# LAYOUT.net
KiCad netlist of a schematic drawn in EAGLE
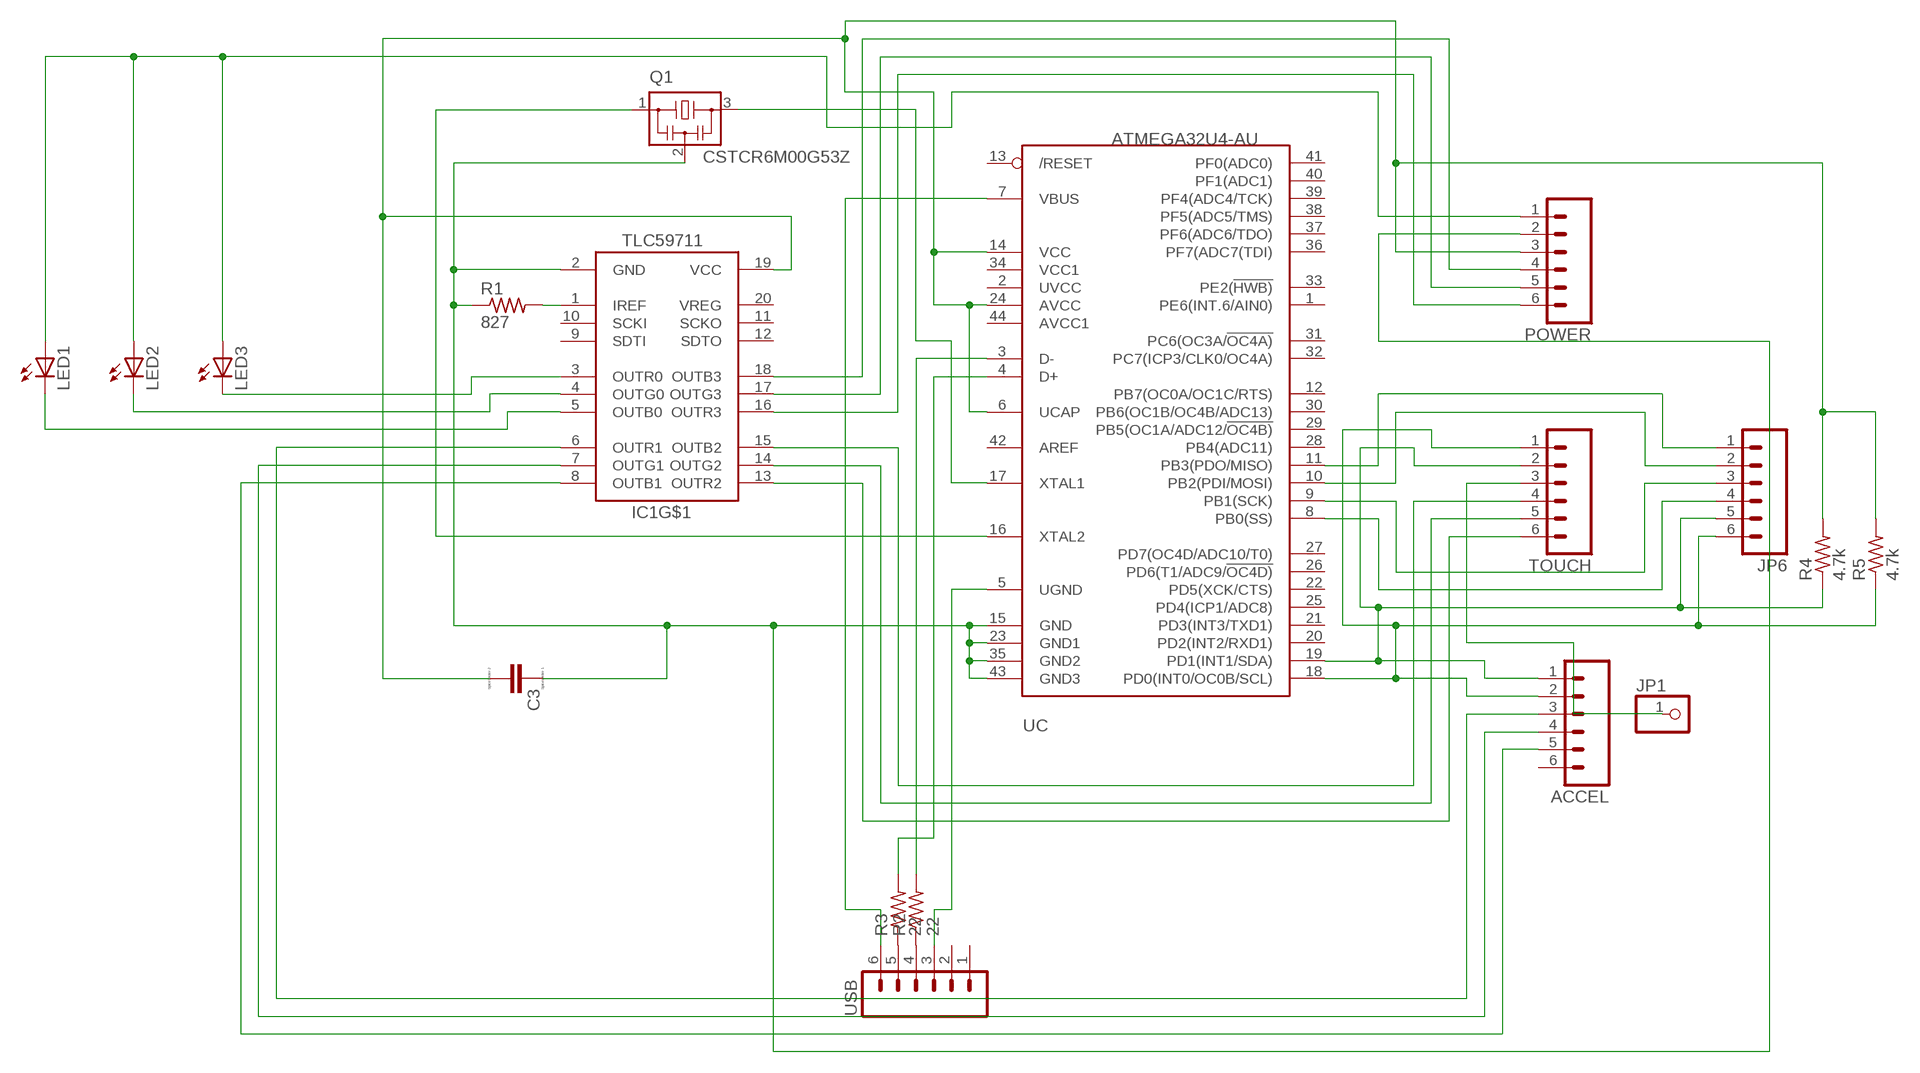
[diagram p0: schematic, sheet 1]

(export (version "E")
  (design (tool "Eeschema 10.0.6"))
  (components
    (comp (ref "ACCEL")
      (value "M06SMD-STRAIGHT")
      (footprint "eagle-import:1X06_SMD_STRAIGHT")
      (libsource (lib "eagle-import") (part "M06SMD-STRAIGHT"))
    )
    (comp (ref "C3")
      (value "CC0603")
      (footprint "eagle-import:C0603")
      (libsource (lib "eagle-import") (part "CC0603"))
    )
    (comp (ref "IC1")
      (value "TLC59711")
      (footprint "eagle-import:HTSSOP20DAP")
      (libsource (lib "eagle-import") (part "TLC59711"))
    )
    (comp (ref "JP1")
      (value "PINHD-1X1")
      (footprint "eagle-import:1X01")
      (libsource (lib "eagle-import") (part "PINHD-1X1"))
    )
    (comp (ref "JP6")
      (value "M06SMD-STRAIGHT")
      (footprint "eagle-import:1X06_SMD_STRAIGHT")
      (libsource (lib "eagle-import") (part "M06SMD-STRAIGHT"))
    )
    (comp (ref "LED1")
      (value "LEDP-LCC-4")
      (footprint "eagle-import:P-LCC-4")
      (libsource (lib "eagle-import") (part "LEDP-LCC-4"))
    )
    (comp (ref "LED2")
      (value "LEDP-LCC-4")
      (footprint "eagle-import:P-LCC-4")
      (libsource (lib "eagle-import") (part "LEDP-LCC-4"))
    )
    (comp (ref "LED3")
      (value "LEDP-LCC-4")
      (footprint "eagle-import:P-LCC-4")
      (libsource (lib "eagle-import") (part "LEDP-LCC-4"))
    )
    (comp (ref "POWER")
      (value "M06SMD-STRAIGHT")
      (footprint "eagle-import:1X06_SMD_STRAIGHT")
      (libsource (lib "eagle-import") (part "M06SMD-STRAIGHT"))
    )
    (comp (ref "Q1")
      (value "CSTCR6M00G53Z")
      (footprint "eagle-import:CSTCR6M")
      (fields (field (name "MPN") "CSTCR6M00G53-R0"))
      (libsource (lib "eagle-import") (part "CSTCR6M00G53Z"))
    )
    (comp (ref "R1")
      (value "827")
      (footprint "eagle-import:R0603")
      (libsource (lib "eagle-import") (part "R-US_R0603"))
    )
    (comp (ref "R2")
      (value "22")
      (footprint "eagle-import:R0603")
      (libsource (lib "eagle-import") (part "R-US_R0603"))
    )
    (comp (ref "R3")
      (value "22")
      (footprint "eagle-import:R0603")
      (libsource (lib "eagle-import") (part "R-US_R0603"))
    )
    (comp (ref "R4")
      (value "4.7k")
      (footprint "eagle-import:R0603")
      (libsource (lib "eagle-import") (part "R-US_R0603"))
    )
    (comp (ref "R5")
      (value "4.7k")
      (footprint "eagle-import:R0603")
      (libsource (lib "eagle-import") (part "R-US_R0603"))
    )
    (comp (ref "TOUCH")
      (value "M06SMD-STRAIGHT")
      (footprint "eagle-import:1X06_SMD_STRAIGHT")
      (libsource (lib "eagle-import") (part "M06SMD-STRAIGHT"))
    )
    (comp (ref "UC")
      (value "ATMEGA32U4-AU")
      (footprint "eagle-import:TQFP44")
      (libsource (lib "eagle-import") (part "ATMEGA32U4-AU"))
    )
    (comp (ref "USB")
      (value "M06SMD-STRAIGHT")
      (footprint "eagle-import:1X06_SMD_STRAIGHT")
      (libsource (lib "eagle-import") (part "M06SMD-STRAIGHT"))
    )
  )
  (nets
    (net (code "1") (name "Net-(IC1A-GND)") (class "Default")
      (node (ref "C3") (pin "1") (pinfunction "1_1") (pintype "passive"))
      (node (ref "IC1") (pin "2") (pinfunction "GND_2") (pintype "power_in"))
      (node (ref "POWER") (pin "2") (pinfunction "2_2") (pintype "passive"))
      (node (ref "Q1") (pin "2") (pinfunction "2_2") (pintype "passive"))
      (node (ref "R1") (pin "1") (pinfunction "1_1") (pintype "passive"))
      (node (ref "UC") (pin "15") (pinfunction "GND_15") (pintype "bidirectional"))
      (node (ref "UC") (pin "23") (pinfunction "GND1_23") (pintype "bidirectional"))
      (node (ref "UC") (pin "35") (pinfunction "GND2_35") (pintype "bidirectional"))
      (node (ref "UC") (pin "43") (pinfunction "GND3_43") (pintype "bidirectional"))
    )
    (net (code "2") (name "Net-(IC1A-IREF)") (class "Default")
      (node (ref "IC1") (pin "1") (pinfunction "IREF_1") (pintype "bidirectional"))
      (node (ref "R1") (pin "2") (pinfunction "2_2") (pintype "passive"))
    )
    (net (code "3") (name "Net-(IC1A-OUTB0)") (class "Default")
      (node (ref "IC1") (pin "5") (pinfunction "OUTB0_5") (pintype "open_collector"))
      (node (ref "LED1") (pin "C@4") (pinfunction "C_C@4") (pintype "passive"))
    )
    (net (code "4") (name "Net-(IC1A-OUTB1)") (class "Default")
      (node (ref "ACCEL") (pin "5") (pinfunction "5_5") (pintype "passive"))
      (node (ref "IC1") (pin "8") (pinfunction "OUTB1_8") (pintype "open_collector"))
    )
    (net (code "5") (name "Net-(IC1A-OUTB2)") (class "Default")
      (node (ref "IC1") (pin "15") (pinfunction "OUTB2_15") (pintype "open_collector"))
      (node (ref "TOUCH") (pin "4") (pinfunction "4_4") (pintype "passive"))
    )
    (net (code "6") (name "Net-(IC1A-OUTB3)") (class "Default")
      (node (ref "IC1") (pin "18") (pinfunction "OUTB3_18") (pintype "open_collector"))
      (node (ref "POWER") (pin "4") (pinfunction "4_4") (pintype "passive"))
    )
    (net (code "7") (name "Net-(IC1A-OUTG0)") (class "Default")
      (node (ref "IC1") (pin "4") (pinfunction "OUTG0_4") (pintype "open_collector"))
      (node (ref "LED2") (pin "C@4") (pinfunction "C_C@4") (pintype "passive"))
    )
    (net (code "8") (name "Net-(IC1A-OUTG1)") (class "Default")
      (node (ref "ACCEL") (pin "4") (pinfunction "4_4") (pintype "passive"))
      (node (ref "IC1") (pin "7") (pinfunction "OUTG1_7") (pintype "open_collector"))
    )
    (net (code "9") (name "Net-(IC1A-OUTG2)") (class "Default")
      (node (ref "IC1") (pin "14") (pinfunction "OUTG2_14") (pintype "open_collector"))
      (node (ref "TOUCH") (pin "5") (pinfunction "5_5") (pintype "passive"))
    )
    (net (code "10") (name "Net-(IC1A-OUTG3)") (class "Default")
      (node (ref "IC1") (pin "17") (pinfunction "OUTG3_17") (pintype "open_collector"))
      (node (ref "POWER") (pin "5") (pinfunction "5_5") (pintype "passive"))
    )
    (net (code "11") (name "Net-(IC1A-OUTR0)") (class "Default")
      (node (ref "IC1") (pin "3") (pinfunction "OUTR0_3") (pintype "open_collector"))
      (node (ref "LED3") (pin "C@4") (pinfunction "C_C@4") (pintype "passive"))
    )
    (net (code "12") (name "Net-(IC1A-OUTR1)") (class "Default")
      (node (ref "ACCEL") (pin "3") (pinfunction "3_3") (pintype "passive"))
      (node (ref "IC1") (pin "6") (pinfunction "OUTR1_6") (pintype "open_collector"))
    )
    (net (code "13") (name "Net-(IC1A-OUTR2)") (class "Default")
      (node (ref "IC1") (pin "13") (pinfunction "OUTR2_13") (pintype "open_collector"))
      (node (ref "TOUCH") (pin "6") (pinfunction "6_6") (pintype "passive"))
    )
    (net (code "14") (name "Net-(IC1A-OUTR3)") (class "Default")
      (node (ref "IC1") (pin "16") (pinfunction "OUTR3_16") (pintype "open_collector"))
      (node (ref "POWER") (pin "6") (pinfunction "6_6") (pintype "passive"))
    )
    (net (code "15") (name "Net-(IC1A-VCC)") (class "Default")
      (node (ref "C3") (pin "2") (pinfunction "2_2") (pintype "passive"))
      (node (ref "IC1") (pin "19") (pinfunction "VCC_19") (pintype "power_in"))
      (node (ref "POWER") (pin "3") (pinfunction "3_3") (pintype "passive"))
      (node (ref "R4") (pin "2") (pinfunction "2_2") (pintype "passive"))
      (node (ref "R5") (pin "2") (pinfunction "2_2") (pintype "passive"))
      (node (ref "UC") (pin "14") (pinfunction "VCC_14") (pintype "bidirectional"))
      (node (ref "UC") (pin "24") (pinfunction "AVCC_24") (pintype "bidirectional"))
      (node (ref "UC") (pin "6") (pinfunction "UCAP_6") (pintype "bidirectional"))
    )
    (net (code "16") (name "Net-(JP1-Pad1)") (class "Default")
      (node (ref "JP1") (pin "1") (pinfunction "1_1") (pintype "passive"))
      (node (ref "TOUCH") (pin "3") (pinfunction "3_3") (pintype "passive"))
    )
    (net (code "17") (name "Net-(LED1-PadA)") (class "Default")
      (node (ref "LED1") (pin "A") (pinfunction "A_A") (pintype "passive"))
      (node (ref "LED2") (pin "A") (pinfunction "A_A") (pintype "passive"))
      (node (ref "LED3") (pin "A") (pinfunction "A_A") (pintype "passive"))
      (node (ref "POWER") (pin "1") (pinfunction "1_1") (pintype "passive"))
    )
    (net (code "18") (name "Net-(R2-Pad1)") (class "Default")
      (node (ref "R2") (pin "1") (pinfunction "1_1") (pintype "passive"))
      (node (ref "USB") (pin "4") (pinfunction "4_4") (pintype "passive"))
    )
    (net (code "19") (name "Net-(R3-Pad1)") (class "Default")
      (node (ref "R3") (pin "1") (pinfunction "1_1") (pintype "passive"))
      (node (ref "USB") (pin "5") (pinfunction "5_5") (pintype "passive"))
    )
    (net (code "20") (name "Net-(UC-D+)") (class "Default")
      (node (ref "R3") (pin "2") (pinfunction "2_2") (pintype "passive"))
      (node (ref "UC") (pin "4") (pinfunction "D+_4") (pintype "bidirectional"))
    )
    (net (code "21") (name "Net-(UC-D-)") (class "Default")
      (node (ref "R2") (pin "2") (pinfunction "2_2") (pintype "passive"))
      (node (ref "UC") (pin "3") (pinfunction "D-_3") (pintype "bidirectional"))
    )
    (net (code "22") (name "Net-(UC-PB0(SS))") (class "Default")
      (node (ref "JP6") (pin "4") (pinfunction "4_4") (pintype "passive"))
      (node (ref "UC") (pin "8") (pinfunction "PB0(SS)_8") (pintype "bidirectional"))
    )
    (net (code "23") (name "Net-(UC-PB1(SCK))") (class "Default")
      (node (ref "JP6") (pin "3") (pinfunction "3_3") (pintype "passive"))
      (node (ref "UC") (pin "9") (pinfunction "PB1(SCK)_9") (pintype "bidirectional"))
    )
    (net (code "24") (name "Net-(UC-PB2(PDI{slash}MOSI))") (class "Default")
      (node (ref "JP6") (pin "2") (pinfunction "2_2") (pintype "passive"))
      (node (ref "UC") (pin "10") (pinfunction "PB2(PDI/MOSI)_10") (pintype "bidirectional"))
    )
    (net (code "25") (name "Net-(UC-PB3(PDO{slash}MISO))") (class "Default")
      (node (ref "JP6") (pin "1") (pinfunction "1_1") (pintype "passive"))
      (node (ref "UC") (pin "11") (pinfunction "PB3(PDO/MISO)_11") (pintype "bidirectional"))
    )
    (net (code "26") (name "Net-(UC-PD0(INT0{slash}OC0B{slash}SCL))") (class "Default")
      (node (ref "ACCEL") (pin "2") (pinfunction "2_2") (pintype "passive"))
      (node (ref "JP6") (pin "6") (pinfunction "6_6") (pintype "passive"))
      (node (ref "R5") (pin "1") (pinfunction "1_1") (pintype "passive"))
      (node (ref "TOUCH") (pin "1") (pinfunction "1_1") (pintype "passive"))
      (node (ref "UC") (pin "18") (pinfunction "PD0(INT0/OC0B/SCL)_18") (pintype "bidirectional"))
    )
    (net (code "27") (name "Net-(UC-PD1(INT1{slash}SDA))") (class "Default")
      (node (ref "ACCEL") (pin "1") (pinfunction "1_1") (pintype "passive"))
      (node (ref "JP6") (pin "5") (pinfunction "5_5") (pintype "passive"))
      (node (ref "R4") (pin "1") (pinfunction "1_1") (pintype "passive"))
      (node (ref "TOUCH") (pin "2") (pinfunction "2_2") (pintype "passive"))
      (node (ref "UC") (pin "19") (pinfunction "PD1(INT1/SDA)_19") (pintype "bidirectional"))
    )
    (net (code "28") (name "Net-(UC-UGND)") (class "Default")
      (node (ref "UC") (pin "5") (pinfunction "UGND_5") (pintype "bidirectional"))
      (node (ref "USB") (pin "3") (pinfunction "3_3") (pintype "passive"))
    )
    (net (code "29") (name "Net-(UC-VBUS)") (class "Default")
      (node (ref "UC") (pin "7") (pinfunction "VBUS_7") (pintype "bidirectional"))
      (node (ref "USB") (pin "6") (pinfunction "6_6") (pintype "passive"))
    )
    (net (code "30") (name "Net-(UC-XTAL1)") (class "Default")
      (node (ref "Q1") (pin "3") (pinfunction "3_3") (pintype "passive"))
      (node (ref "UC") (pin "17") (pinfunction "XTAL1_17") (pintype "bidirectional"))
    )
    (net (code "31") (name "Net-(UC-XTAL2)") (class "Default")
      (node (ref "Q1") (pin "1") (pinfunction "1_1") (pintype "passive"))
      (node (ref "UC") (pin "16") (pinfunction "XTAL2_16") (pintype "bidirectional"))
    )
    (net (code "32") (name "unconnected-(ACCEL-Pad6)") (class "Default")
      (node (ref "ACCEL") (pin "6") (pinfunction "6_6") (pintype "passive"))
    )
    (net (code "33") (name "unconnected-(IC1A-SCKI-Pad10)") (class "Default")
      (node (ref "IC1") (pin "10") (pinfunction "SCKI_10") (pintype "input"))
    )
    (net (code "34") (name "unconnected-(IC1A-SCKO-Pad11)") (class "Default")
      (node (ref "IC1") (pin "11") (pinfunction "SCKO_11") (pintype "output"))
    )
    (net (code "35") (name "unconnected-(IC1A-SDTI-Pad9)") (class "Default")
      (node (ref "IC1") (pin "9") (pinfunction "SDTI_9") (pintype "input"))
    )
    (net (code "36") (name "unconnected-(IC1A-SDTO-Pad12)") (class "Default")
      (node (ref "IC1") (pin "12") (pinfunction "SDTO_12") (pintype "output"))
    )
    (net (code "37") (name "unconnected-(IC1A-VREG-Pad20)") (class "Default")
      (node (ref "IC1") (pin "20") (pinfunction "VREG_20") (pintype "bidirectional"))
    )
    (net (code "38") (name "unconnected-(UC-AREF-Pad42)") (class "Default")
      (node (ref "UC") (pin "42") (pinfunction "AREF_42") (pintype "bidirectional"))
    )
    (net (code "39") (name "unconnected-(UC-AVCC1-Pad44)") (class "Default")
      (node (ref "UC") (pin "44") (pinfunction "AVCC1_44") (pintype "bidirectional"))
    )
    (net (code "40") (name "unconnected-(UC-PB4(ADC11)-Pad28)") (class "Default")
      (node (ref "UC") (pin "28") (pinfunction "PB4(ADC11)_28") (pintype "bidirectional"))
    )
    (net (code "41") (name "unconnected-(UC-PB5(OC1A{slash}ADC12{slash}~{OC4B})-Pad29)") (class "Default")
      (node (ref "UC") (pin "29") (pinfunction "PB5(OC1A/ADC12/~{OC4B})_29") (pintype "bidirectional"))
    )
    (net (code "42") (name "unconnected-(UC-PB6(OC1B{slash}OC4B{slash}ADC13)-Pad30)") (class "Default")
      (node (ref "UC") (pin "30") (pinfunction "PB6(OC1B/OC4B/ADC13)_30") (pintype "bidirectional"))
    )
    (net (code "43") (name "unconnected-(UC-PB7(OC0A{slash}OC1C{slash}RTS)-Pad12)") (class "Default")
      (node (ref "UC") (pin "12") (pinfunction "PB7(OC0A/OC1C/RTS)_12") (pintype "bidirectional"))
    )
    (net (code "44") (name "unconnected-(UC-PC6(OC3A{slash}~{OC4A})-Pad31)") (class "Default")
      (node (ref "UC") (pin "31") (pinfunction "PC6(OC3A/~{OC4A})_31") (pintype "bidirectional"))
    )
    (net (code "45") (name "unconnected-(UC-PC7(ICP3{slash}CLK0{slash}OC4A)-Pad32)") (class "Default")
      (node (ref "UC") (pin "32") (pinfunction "PC7(ICP3/CLK0/OC4A)_32") (pintype "bidirectional"))
    )
    (net (code "46") (name "unconnected-(UC-PD2(INT2{slash}RXD1)-Pad20)") (class "Default")
      (node (ref "UC") (pin "20") (pinfunction "PD2(INT2/RXD1)_20") (pintype "bidirectional"))
    )
    (net (code "47") (name "unconnected-(UC-PD3(INT3{slash}TXD1)-Pad21)") (class "Default")
      (node (ref "UC") (pin "21") (pinfunction "PD3(INT3/TXD1)_21") (pintype "bidirectional"))
    )
    (net (code "48") (name "unconnected-(UC-PD4(ICP1{slash}ADC8)-Pad25)") (class "Default")
      (node (ref "UC") (pin "25") (pinfunction "PD4(ICP1/ADC8)_25") (pintype "bidirectional"))
    )
    (net (code "49") (name "unconnected-(UC-PD5(XCK{slash}CTS)-Pad22)") (class "Default")
      (node (ref "UC") (pin "22") (pinfunction "PD5(XCK/CTS)_22") (pintype "bidirectional"))
    )
    (net (code "50") (name "unconnected-(UC-PD6(T1{slash}ADC9{slash}~{OC4D})-Pad26)") (class "Default")
      (node (ref "UC") (pin "26") (pinfunction "PD6(T1/ADC9/~{OC4D})_26") (pintype "bidirectional"))
    )
    (net (code "51") (name "unconnected-(UC-PD7(OC4D{slash}ADC10{slash}T0)-Pad27)") (class "Default")
      (node (ref "UC") (pin "27") (pinfunction "PD7(OC4D/ADC10/T0)_27") (pintype "bidirectional"))
    )
    (net (code "52") (name "unconnected-(UC-PE2(~{HWB})-Pad33)") (class "Default")
      (node (ref "UC") (pin "33") (pinfunction "PE2(~{HWB})_33") (pintype "bidirectional"))
    )
    (net (code "53") (name "unconnected-(UC-PE6(INT.6{slash}AIN0)-Pad1)") (class "Default")
      (node (ref "UC") (pin "1") (pinfunction "PE6(INT.6/AIN0)_1") (pintype "bidirectional"))
    )
    (net (code "54") (name "unconnected-(UC-PF0(ADC0)-Pad41)") (class "Default")
      (node (ref "UC") (pin "41") (pinfunction "PF0(ADC0)_41") (pintype "bidirectional"))
    )
    (net (code "55") (name "unconnected-(UC-PF1(ADC1)-Pad40)") (class "Default")
      (node (ref "UC") (pin "40") (pinfunction "PF1(ADC1)_40") (pintype "bidirectional"))
    )
    (net (code "56") (name "unconnected-(UC-PF4(ADC4{slash}TCK)-Pad39)") (class "Default")
      (node (ref "UC") (pin "39") (pinfunction "PF4(ADC4/TCK)_39") (pintype "bidirectional"))
    )
    (net (code "57") (name "unconnected-(UC-PF5(ADC5{slash}TMS)-Pad38)") (class "Default")
      (node (ref "UC") (pin "38") (pinfunction "PF5(ADC5/TMS)_38") (pintype "bidirectional"))
    )
    (net (code "58") (name "unconnected-(UC-PF6(ADC6{slash}TDO)-Pad37)") (class "Default")
      (node (ref "UC") (pin "37") (pinfunction "PF6(ADC6/TDO)_37") (pintype "bidirectional"))
    )
    (net (code "59") (name "unconnected-(UC-PF7(ADC7(TDI)-Pad36)") (class "Default")
      (node (ref "UC") (pin "36") (pinfunction "PF7(ADC7(TDI)_36") (pintype "bidirectional"))
    )
    (net (code "60") (name "unconnected-(UC-UVCC-Pad2)") (class "Default")
      (node (ref "UC") (pin "2") (pinfunction "UVCC_2") (pintype "bidirectional"))
    )
    (net (code "61") (name "unconnected-(UC-VCC1-Pad34)") (class "Default")
      (node (ref "UC") (pin "34") (pinfunction "VCC1_34") (pintype "bidirectional"))
    )
    (net (code "62") (name "unconnected-(UC-{slash}RESET-Pad13)") (class "Default")
      (node (ref "UC") (pin "13") (pinfunction "/RESET_13") (pintype "bidirectional"))
    )
    (net (code "63") (name "unconnected-(USB-Pad1)") (class "Default")
      (node (ref "USB") (pin "1") (pinfunction "1_1") (pintype "passive"))
    )
    (net (code "64") (name "unconnected-(USB-Pad2)") (class "Default")
      (node (ref "USB") (pin "2") (pinfunction "2_2") (pintype "passive"))
    )
  )
)
